# untitled.net
KiCad netlist of a schematic drawn in EAGLE
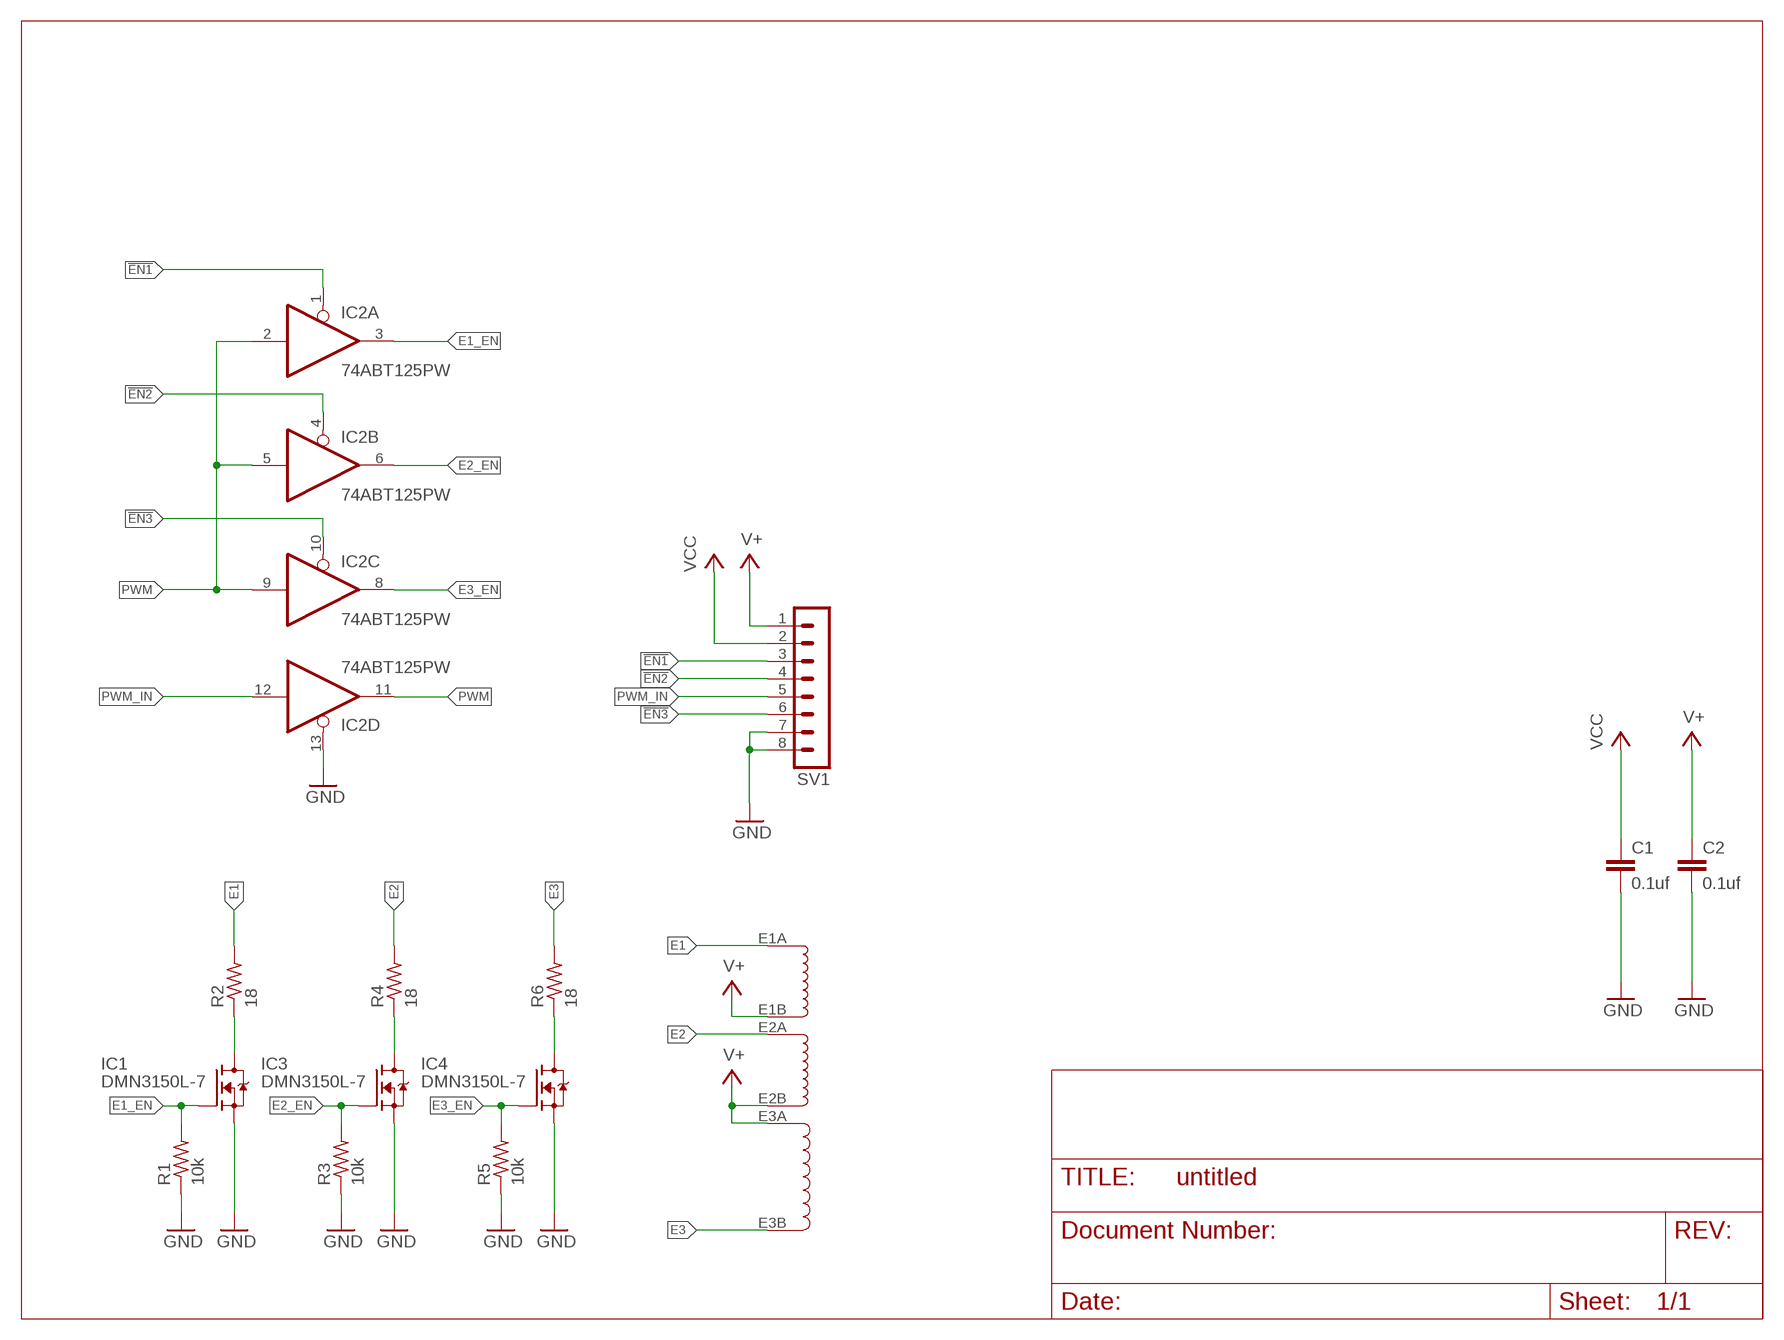
[diagram p0: schematic, sheet 1]

(export (version "E")
  (design (tool "Eeschema 10.0.6"))
  (components
    (comp (ref "C1")
      (value "0.1uf")
      (footprint "eagle-import:C0603")
      (libsource (lib "eagle-import") (part "C-EUC0603"))
    )
    (comp (ref "C2")
      (value "0.1uf")
      (footprint "eagle-import:C0603")
      (libsource (lib "eagle-import") (part "C-EUC0603"))
    )
    (comp (ref "IC1")
      (value "DMN3150L-7")
      (footprint "eagle-import:SOT23")
      (libsource (lib "eagle-import") (part "DS31126"))
    )
    (comp (ref "IC2")
      (value "74ABT125PW")
      (footprint "eagle-import:TSSOP14")
      (libsource (lib "eagle-import") (part "74125PWABT"))
    )
    (comp (ref "IC3")
      (value "DMN3150L-7")
      (footprint "eagle-import:SOT23")
      (libsource (lib "eagle-import") (part "DS31126"))
    )
    (comp (ref "IC4")
      (value "DMN3150L-7")
      (footprint "eagle-import:SOT23")
      (libsource (lib "eagle-import") (part "DS31126"))
    )
    (comp (ref "NICR1")
      (value "HOT_WIRE")
      (footprint "eagle-import:LAYOUT_A")
      (libsource (lib "eagle-import") (part "HOT_WIRE"))
    )
    (comp (ref "R1")
      (value "10k")
      (footprint "eagle-import:R0603")
      (libsource (lib "eagle-import") (part "R-US_R0603"))
    )
    (comp (ref "R2")
      (value "18")
      (footprint "eagle-import:R2512W")
      (libsource (lib "eagle-import") (part "R-US_R2512W"))
    )
    (comp (ref "R3")
      (value "10k")
      (footprint "eagle-import:R0603")
      (libsource (lib "eagle-import") (part "R-US_R0603"))
    )
    (comp (ref "R4")
      (value "18")
      (footprint "eagle-import:R2512W")
      (libsource (lib "eagle-import") (part "R-US_R2512W"))
    )
    (comp (ref "R5")
      (value "10k")
      (footprint "eagle-import:R0603")
      (libsource (lib "eagle-import") (part "R-US_R0603"))
    )
    (comp (ref "R6")
      (value "18")
      (footprint "eagle-import:R2512W")
      (libsource (lib "eagle-import") (part "R-US_R2512W"))
    )
    (comp (ref "SV1")
      (value "MA08-1")
      (footprint "eagle-import:MA08-1")
      (libsource (lib "eagle-import") (part "MA08-1"))
    )
  )
  (nets
    (net (code "1") (name "/~{EN1}") (class "Default")
      (node (ref "IC2") (pin "1") (pinfunction "OE_1") (pintype "input"))
      (node (ref "SV1") (pin "3") (pinfunction "3_3") (pintype "passive"))
    )
    (net (code "2") (name "/~{EN2}") (class "Default")
      (node (ref "IC2") (pin "4") (pinfunction "OE_4") (pintype "input"))
      (node (ref "SV1") (pin "4") (pinfunction "4_4") (pintype "passive"))
    )
    (net (code "3") (name "/~{EN3}") (class "Default")
      (node (ref "IC2") (pin "10") (pinfunction "OE_10") (pintype "input"))
      (node (ref "SV1") (pin "6") (pinfunction "6_6") (pintype "passive"))
    )
    (net (code "4") (name "E1") (class "Default")
      (node (ref "NICR1") (pin "E1A") (pinfunction "P$1_E1A") (pintype "bidirectional"))
      (node (ref "R2") (pin "2") (pinfunction "2_2") (pintype "passive"))
    )
    (net (code "5") (name "E1_EN") (class "Default")
      (node (ref "IC1") (pin "G") (pinfunction "G_G") (pintype "passive"))
      (node (ref "IC2") (pin "3") (pinfunction "O_3") (pintype "tri_state"))
      (node (ref "R1") (pin "2") (pinfunction "2_2") (pintype "passive"))
    )
    (net (code "6") (name "E2") (class "Default")
      (node (ref "NICR1") (pin "E2A") (pinfunction "P$1_E2A") (pintype "bidirectional"))
      (node (ref "R4") (pin "2") (pinfunction "2_2") (pintype "passive"))
    )
    (net (code "7") (name "E2_EN") (class "Default")
      (node (ref "IC2") (pin "6") (pinfunction "O_6") (pintype "tri_state"))
      (node (ref "IC3") (pin "G") (pinfunction "G_G") (pintype "passive"))
      (node (ref "R3") (pin "2") (pinfunction "2_2") (pintype "passive"))
    )
    (net (code "8") (name "E3") (class "Default")
      (node (ref "NICR1") (pin "E3B") (pinfunction "P$2_E3B") (pintype "bidirectional"))
      (node (ref "R6") (pin "2") (pinfunction "2_2") (pintype "passive"))
    )
    (net (code "9") (name "E3_EN") (class "Default")
      (node (ref "IC2") (pin "8") (pinfunction "O_8") (pintype "tri_state"))
      (node (ref "IC4") (pin "G") (pinfunction "G_G") (pintype "passive"))
      (node (ref "R5") (pin "2") (pinfunction "2_2") (pintype "passive"))
    )
    (net (code "10") (name "GND") (class "Default")
      (node (ref "C1") (pin "2") (pinfunction "2_2") (pintype "passive"))
      (node (ref "C2") (pin "2") (pinfunction "2_2") (pintype "passive"))
      (node (ref "IC1") (pin "S") (pinfunction "S_S") (pintype "passive"))
      (node (ref "IC2") (pin "13") (pinfunction "OE_13") (pintype "input"))
      (node (ref "IC3") (pin "S") (pinfunction "S_S") (pintype "passive"))
      (node (ref "IC4") (pin "S") (pinfunction "S_S") (pintype "passive"))
      (node (ref "R1") (pin "1") (pinfunction "1_1") (pintype "passive"))
      (node (ref "R3") (pin "1") (pinfunction "1_1") (pintype "passive"))
      (node (ref "R5") (pin "1") (pinfunction "1_1") (pintype "passive"))
      (node (ref "SV1") (pin "7") (pinfunction "7_7") (pintype "passive"))
      (node (ref "SV1") (pin "8") (pinfunction "8_8") (pintype "passive"))
    )
    (net (code "11") (name "Net-(IC1-PadD)") (class "Default")
      (node (ref "IC1") (pin "D") (pinfunction "D_D") (pintype "passive"))
      (node (ref "R2") (pin "1") (pinfunction "1_1") (pintype "passive"))
    )
    (net (code "12") (name "Net-(IC3-PadD)") (class "Default")
      (node (ref "IC3") (pin "D") (pinfunction "D_D") (pintype "passive"))
      (node (ref "R4") (pin "1") (pinfunction "1_1") (pintype "passive"))
    )
    (net (code "13") (name "Net-(IC4-PadD)") (class "Default")
      (node (ref "IC4") (pin "D") (pinfunction "D_D") (pintype "passive"))
      (node (ref "R6") (pin "1") (pinfunction "1_1") (pintype "passive"))
    )
    (net (code "14") (name "PWM") (class "Default")
      (node (ref "IC2") (pin "11") (pinfunction "O_11") (pintype "tri_state"))
      (node (ref "IC2") (pin "2") (pinfunction "I_2") (pintype "input"))
      (node (ref "IC2") (pin "5") (pinfunction "I_5") (pintype "input"))
      (node (ref "IC2") (pin "9") (pinfunction "I_9") (pintype "input"))
    )
    (net (code "15") (name "PWM_IN") (class "Default")
      (node (ref "IC2") (pin "12") (pinfunction "I_12") (pintype "input"))
      (node (ref "SV1") (pin "5") (pinfunction "5_5") (pintype "passive"))
    )
    (net (code "16") (name "V+") (class "Default")
      (node (ref "C2") (pin "1") (pinfunction "1_1") (pintype "passive"))
      (node (ref "NICR1") (pin "E1B") (pinfunction "P$2_E1B") (pintype "bidirectional"))
      (node (ref "NICR1") (pin "E2B") (pinfunction "P$2_E2B") (pintype "bidirectional"))
      (node (ref "NICR1") (pin "E3A") (pinfunction "P$1_E3A") (pintype "bidirectional"))
      (node (ref "SV1") (pin "1") (pinfunction "1_1") (pintype "passive"))
    )
    (net (code "17") (name "VCC") (class "Default")
      (node (ref "C1") (pin "1") (pinfunction "1_1") (pintype "passive"))
      (node (ref "SV1") (pin "2") (pinfunction "2_2") (pintype "passive"))
    )
  )
)
